# GLogger-shield.net
KiCad netlist of a schematic drawn in EAGLE
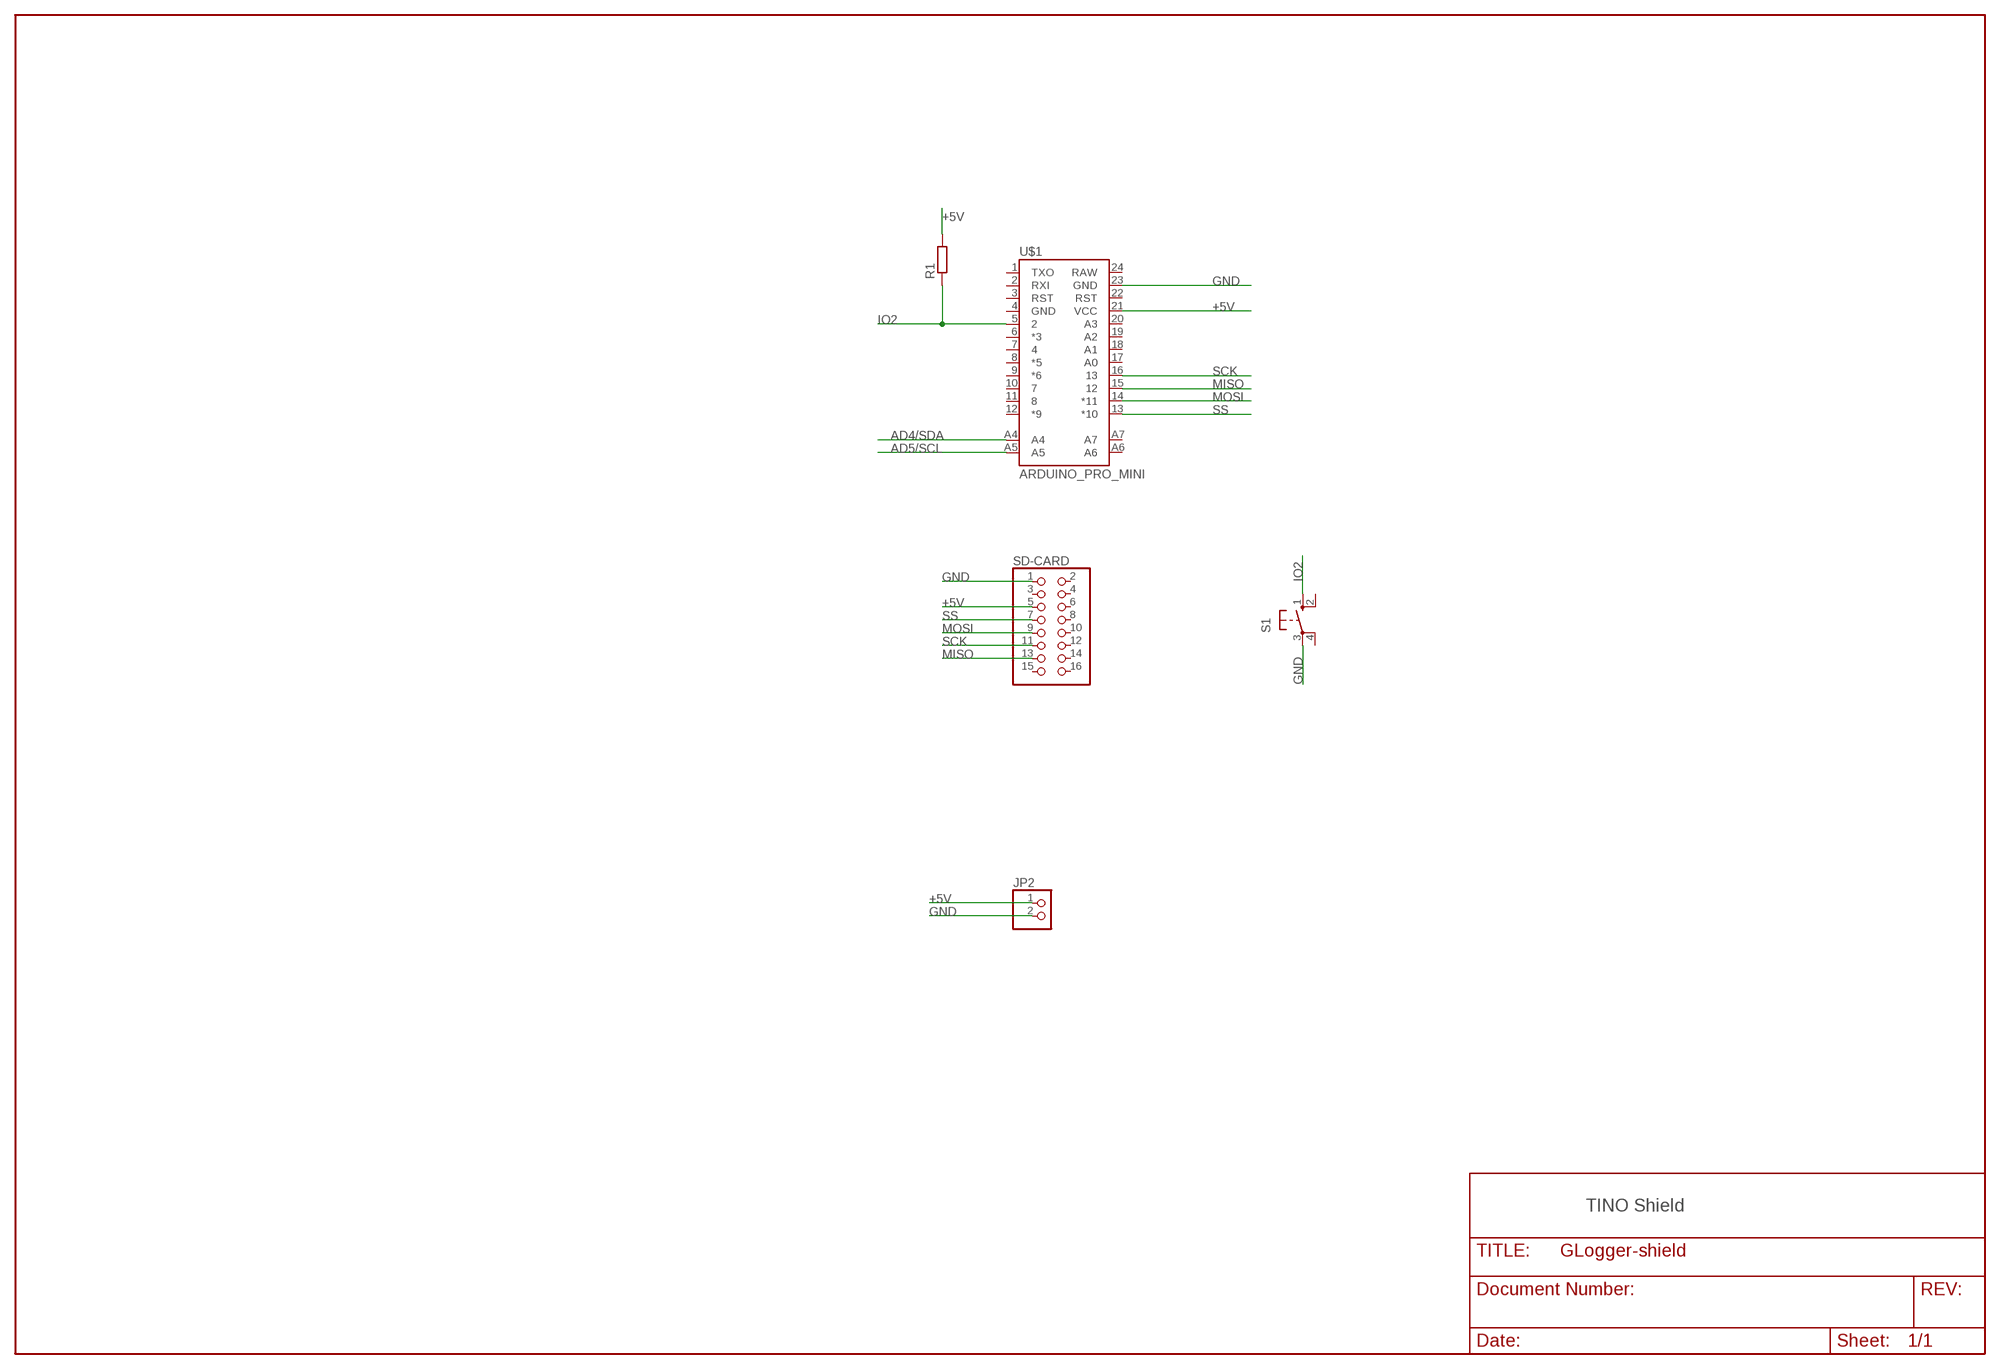
[diagram p0: schematic, sheet 1]

(export (version "E")
  (design (tool "Eeschema 10.0.6"))
  (components
    (comp (ref "JP2")
      (value "PINHD-1X2")
      (footprint "eagle-import:1X02")
      (libsource (lib "eagle-import") (part "PINHD-1X2"))
    )
    (comp (ref "R1")
      (value "R-EU_0207/10")
      (footprint "eagle-import:0207_10")
      (libsource (lib "eagle-import") (part "R-EU_0207/10"))
    )
    (comp (ref "S1")
      (value "40-XX-ROUND")
      (footprint "eagle-import:B3F-40XX-ROUND")
      (libsource (lib "eagle-import") (part "40-XX-ROUND"))
    )
    (comp (ref "SD-CARD")
      (value "PINHD-2X8")
      (footprint "eagle-import:2X08")
      (libsource (lib "eagle-import") (part "PINHD-2X8"))
    )
    (comp (ref "U$1")
      (value "ARDUINO_PRO_MINI")
      (footprint "eagle-import:ARDUINO_PRO_MINI")
      (libsource (lib "eagle-import") (part "ARDUINO_PRO_MINI"))
    )
  )
  (nets
    (net (code "1") (name "/+5V") (class "Default")
      (node (ref "JP2") (pin "1") (pinfunction "1_1") (pintype "passive"))
      (node (ref "R1") (pin "2") (pinfunction "2_2") (pintype "passive"))
      (node (ref "SD-CARD") (pin "5") (pinfunction "5_5") (pintype "passive"))
      (node (ref "U$1") (pin "21") (pinfunction "VCC_21") (pintype "bidirectional"))
    )
    (net (code "2") (name "/AD4{slash}SDA") (class "Default")
      (node (ref "U$1") (pin "A4") (pinfunction "A4_A4") (pintype "bidirectional"))
    )
    (net (code "3") (name "/AD5{slash}SCL") (class "Default")
      (node (ref "U$1") (pin "A5") (pinfunction "A5_A5") (pintype "bidirectional"))
    )
    (net (code "4") (name "/GND") (class "Default")
      (node (ref "JP2") (pin "2") (pinfunction "2_2") (pintype "passive"))
      (node (ref "S1") (pin "3") (pinfunction "P_3") (pintype "passive"))
      (node (ref "SD-CARD") (pin "1") (pinfunction "1_1") (pintype "passive"))
      (node (ref "U$1") (pin "23") (pinfunction "GND_23") (pintype "bidirectional"))
    )
    (net (code "5") (name "/IO2") (class "Default")
      (node (ref "R1") (pin "1") (pinfunction "1_1") (pintype "passive"))
      (node (ref "S1") (pin "1") (pinfunction "S_1") (pintype "passive"))
      (node (ref "U$1") (pin "5") (pinfunction "2_5") (pintype "bidirectional"))
    )
    (net (code "6") (name "/MISO") (class "Default")
      (node (ref "SD-CARD") (pin "13") (pinfunction "13_13") (pintype "passive"))
      (node (ref "U$1") (pin "15") (pinfunction "12_15") (pintype "bidirectional"))
    )
    (net (code "7") (name "/MOSI") (class "Default")
      (node (ref "SD-CARD") (pin "9") (pinfunction "9_9") (pintype "passive"))
      (node (ref "U$1") (pin "14") (pinfunction "*11_14") (pintype "bidirectional"))
    )
    (net (code "8") (name "/SCK") (class "Default")
      (node (ref "SD-CARD") (pin "11") (pinfunction "11_11") (pintype "passive"))
      (node (ref "U$1") (pin "16") (pinfunction "13_16") (pintype "bidirectional"))
    )
    (net (code "9") (name "/SS") (class "Default")
      (node (ref "SD-CARD") (pin "7") (pinfunction "7_7") (pintype "passive"))
      (node (ref "U$1") (pin "13") (pinfunction "*10_13") (pintype "bidirectional"))
    )
    (net (code "10") (name "unconnected-(S1-P1-Pad4)") (class "Default")
      (node (ref "S1") (pin "4") (pinfunction "P1_4") (pintype "passive"))
    )
    (net (code "11") (name "unconnected-(S1-S1-Pad2)") (class "Default")
      (node (ref "S1") (pin "2") (pinfunction "S1_2") (pintype "passive"))
    )
    (net (code "12") (name "unconnected-(SD-CARD-Pad2)") (class "Default")
      (node (ref "SD-CARD") (pin "2") (pinfunction "2_2") (pintype "passive"))
    )
    (net (code "13") (name "unconnected-(SD-CARD-Pad3)") (class "Default")
      (node (ref "SD-CARD") (pin "3") (pinfunction "3_3") (pintype "passive"))
    )
    (net (code "14") (name "unconnected-(SD-CARD-Pad4)") (class "Default")
      (node (ref "SD-CARD") (pin "4") (pinfunction "4_4") (pintype "passive"))
    )
    (net (code "15") (name "unconnected-(SD-CARD-Pad6)") (class "Default")
      (node (ref "SD-CARD") (pin "6") (pinfunction "6_6") (pintype "passive"))
    )
    (net (code "16") (name "unconnected-(SD-CARD-Pad8)") (class "Default")
      (node (ref "SD-CARD") (pin "8") (pinfunction "8_8") (pintype "passive"))
    )
    (net (code "17") (name "unconnected-(SD-CARD-Pad10)") (class "Default")
      (node (ref "SD-CARD") (pin "10") (pinfunction "10_10") (pintype "passive"))
    )
    (net (code "18") (name "unconnected-(SD-CARD-Pad12)") (class "Default")
      (node (ref "SD-CARD") (pin "12") (pinfunction "12_12") (pintype "passive"))
    )
    (net (code "19") (name "unconnected-(SD-CARD-Pad14)") (class "Default")
      (node (ref "SD-CARD") (pin "14") (pinfunction "14_14") (pintype "passive"))
    )
    (net (code "20") (name "unconnected-(SD-CARD-Pad15)") (class "Default")
      (node (ref "SD-CARD") (pin "15") (pinfunction "15_15") (pintype "passive"))
    )
    (net (code "21") (name "unconnected-(SD-CARD-Pad16)") (class "Default")
      (node (ref "SD-CARD") (pin "16") (pinfunction "16_16") (pintype "passive"))
    )
    (net (code "22") (name "unconnected-(U$1-*3-Pad6)") (class "Default")
      (node (ref "U$1") (pin "6") (pinfunction "*3_6") (pintype "bidirectional"))
    )
    (net (code "23") (name "unconnected-(U$1-*5-Pad8)") (class "Default")
      (node (ref "U$1") (pin "8") (pinfunction "*5_8") (pintype "bidirectional"))
    )
    (net (code "24") (name "unconnected-(U$1-*6-Pad9)") (class "Default")
      (node (ref "U$1") (pin "9") (pinfunction "*6_9") (pintype "bidirectional"))
    )
    (net (code "25") (name "unconnected-(U$1-*9-Pad12)") (class "Default")
      (node (ref "U$1") (pin "12") (pinfunction "*9_12") (pintype "bidirectional"))
    )
    (net (code "26") (name "unconnected-(U$1-4-Pad7)") (class "Default")
      (node (ref "U$1") (pin "7") (pinfunction "4_7") (pintype "bidirectional"))
    )
    (net (code "27") (name "unconnected-(U$1-7-Pad10)") (class "Default")
      (node (ref "U$1") (pin "10") (pinfunction "7_10") (pintype "bidirectional"))
    )
    (net (code "28") (name "unconnected-(U$1-8-Pad11)") (class "Default")
      (node (ref "U$1") (pin "11") (pinfunction "8_11") (pintype "bidirectional"))
    )
    (net (code "29") (name "unconnected-(U$1-A0-Pad17)") (class "Default")
      (node (ref "U$1") (pin "17") (pinfunction "A0_17") (pintype "bidirectional"))
    )
    (net (code "30") (name "unconnected-(U$1-A1-Pad18)") (class "Default")
      (node (ref "U$1") (pin "18") (pinfunction "A1_18") (pintype "bidirectional"))
    )
    (net (code "31") (name "unconnected-(U$1-A2-Pad19)") (class "Default")
      (node (ref "U$1") (pin "19") (pinfunction "A2_19") (pintype "bidirectional"))
    )
    (net (code "32") (name "unconnected-(U$1-A3-Pad20)") (class "Default")
      (node (ref "U$1") (pin "20") (pinfunction "A3_20") (pintype "bidirectional"))
    )
    (net (code "33") (name "unconnected-(U$1-GND-Pad4)") (class "Default")
      (node (ref "U$1") (pin "4") (pinfunction "GND_4") (pintype "bidirectional"))
    )
    (net (code "34") (name "unconnected-(U$1-PadA6)") (class "Default")
      (node (ref "U$1") (pin "A6") (pinfunction "A6_A6") (pintype "bidirectional"))
    )
    (net (code "35") (name "unconnected-(U$1-PadA7)") (class "Default")
      (node (ref "U$1") (pin "A7") (pinfunction "A7_A7") (pintype "bidirectional"))
    )
    (net (code "36") (name "unconnected-(U$1-RAW-Pad24)") (class "Default")
      (node (ref "U$1") (pin "24") (pinfunction "RAW_24") (pintype "bidirectional"))
    )
    (net (code "37") (name "unconnected-(U$1-RST-Pad3)") (class "Default")
      (node (ref "U$1") (pin "3") (pinfunction "RST_3") (pintype "bidirectional"))
    )
    (net (code "38") (name "unconnected-(U$1-RST-Pad22)") (class "Default")
      (node (ref "U$1") (pin "22") (pinfunction "RST_22") (pintype "bidirectional"))
    )
    (net (code "39") (name "unconnected-(U$1-RXI-Pad2)") (class "Default")
      (node (ref "U$1") (pin "2") (pinfunction "RXI_2") (pintype "bidirectional"))
    )
    (net (code "40") (name "unconnected-(U$1-TXO-Pad1)") (class "Default")
      (node (ref "U$1") (pin "1") (pinfunction "TXO_1") (pintype "bidirectional"))
    )
  )
)
